# doergreie.net
KiCad netlist of a schematic drawn in Altium Designer
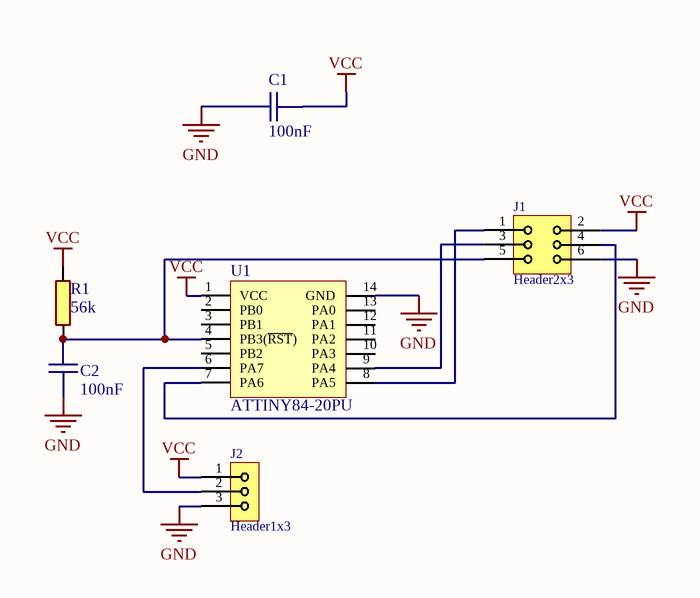
[diagram p0: doergreie.SchDoc]

(export (version "E")
  (design (tool "Eeschema 10.0.6"))
  (components
    (comp (ref "C1")
      (value "100nF")
      (footprint "CAPAR500W50L730T250H650")
      (description "100V plast")
      (libsource (lib "OVLib") (part "CAP"))
    )
    (comp (ref "C2")
      (value "100nF")
      (footprint "CAPAR500W50L730T250H650")
      (description "100V plast")
      (libsource (lib "OVLib") (part "CAP"))
    )
    (comp (ref "J1")
      (value "Header2x3")
      (footprint "HDRV6W64P254_2X3_762X508X900B")
      (libsource (lib "OVLib") (part "Header2x3"))
    )
    (comp (ref "J2")
      (value "Header1x3")
      (footprint "HDRV3W64P254_1X3_762X254X900B")
      (libsource (lib "OVLib") (part "Header1x3"))
    )
    (comp (ref "R1")
      (value "56k")
      (footprint "RESA_0.25W")
      (description "0.25W 1% Generic resistor")
      (libsource (lib "OVLib") (part "Resistor2"))
    )
    (comp (ref "U1") (value "ATTINY84-20PU") (footprint "DIP14") (libsource (lib "OVLib") (part "ATTINY84")))
  )
  (nets
    (net (code "1") (name "GND") (class "Default")
      (node (ref "C1") (pin "1") (pinfunction "1_1") (pintype "passive"))
      (node (ref "C2") (pin "1") (pinfunction "1_1") (pintype "passive"))
      (node (ref "J1") (pin "6") (pinfunction "6_6") (pintype "passive"))
      (node (ref "J2") (pin "3") (pinfunction "3_3") (pintype "passive"))
      (node (ref "U1") (pin "14") (pinfunction "GND_14") (pintype "passive"))
    )
    (net (code "2") (name "Net-(U1-PA4)") (class "Default")
      (node (ref "J1") (pin "3") (pinfunction "3_3") (pintype "passive"))
      (node (ref "U1") (pin "9") (pinfunction "PA4_9") (pintype "passive"))
    )
    (net (code "3") (name "Net-(U1-PA5)") (class "Default")
      (node (ref "J1") (pin "1") (pinfunction "1_1") (pintype "passive"))
      (node (ref "U1") (pin "8") (pinfunction "PA5_8") (pintype "passive"))
    )
    (net (code "4") (name "Net-(U1-PA6)") (class "Default")
      (node (ref "J1") (pin "4") (pinfunction "4_4") (pintype "passive"))
      (node (ref "U1") (pin "7") (pinfunction "PA6_7") (pintype "passive"))
    )
    (net (code "5") (name "Net-(U1-PA7)") (class "Default")
      (node (ref "J2") (pin "2") (pinfunction "2_2") (pintype "passive"))
      (node (ref "U1") (pin "6") (pinfunction "PA7_6") (pintype "passive"))
    )
    (net (code "6") (name "Net-(U1-PB3(~{RST}))") (class "Default")
      (node (ref "C2") (pin "2") (pinfunction "2_2") (pintype "passive"))
      (node (ref "J1") (pin "5") (pinfunction "5_5") (pintype "passive"))
      (node (ref "R1") (pin "1") (pinfunction "1_1") (pintype "passive"))
      (node (ref "U1") (pin "4") (pinfunction "PB3(~{RST})_4") (pintype "passive"))
    )
    (net (code "7") (name "VCC") (class "Default")
      (node (ref "C1") (pin "2") (pinfunction "2_2") (pintype "passive"))
      (node (ref "J1") (pin "2") (pinfunction "2_2") (pintype "passive"))
      (node (ref "J2") (pin "1") (pinfunction "1_1") (pintype "passive"))
      (node (ref "R1") (pin "2") (pinfunction "2_2") (pintype "passive"))
      (node (ref "U1") (pin "1") (pinfunction "VCC_1") (pintype "power_in"))
    )
    (net (code "8") (name "unconnected-(U1-PA0-Pad13)") (class "Default")
      (node (ref "U1") (pin "13") (pinfunction "PA0_13") (pintype "passive"))
    )
    (net (code "9") (name "unconnected-(U1-PA1-Pad12)") (class "Default")
      (node (ref "U1") (pin "12") (pinfunction "PA1_12") (pintype "passive"))
    )
    (net (code "10") (name "unconnected-(U1-PA2-Pad11)") (class "Default")
      (node (ref "U1") (pin "11") (pinfunction "PA2_11") (pintype "passive"))
    )
    (net (code "11") (name "unconnected-(U1-PA3-Pad10)") (class "Default")
      (node (ref "U1") (pin "10") (pinfunction "PA3_10") (pintype "passive"))
    )
    (net (code "12") (name "unconnected-(U1-PB0-Pad2)") (class "Default")
      (node (ref "U1") (pin "2") (pinfunction "PB0_2") (pintype "passive"))
    )
    (net (code "13") (name "unconnected-(U1-PB1-Pad3)") (class "Default")
      (node (ref "U1") (pin "3") (pinfunction "PB1_3") (pintype "passive"))
    )
    (net (code "14") (name "unconnected-(U1-PB2-Pad5)") (class "Default")
      (node (ref "U1") (pin "5") (pinfunction "PB2_5") (pintype "passive"))
    )
  )
)
